# op-synth_0_8.net
KiCad netlist of a schematic drawn in EAGLE
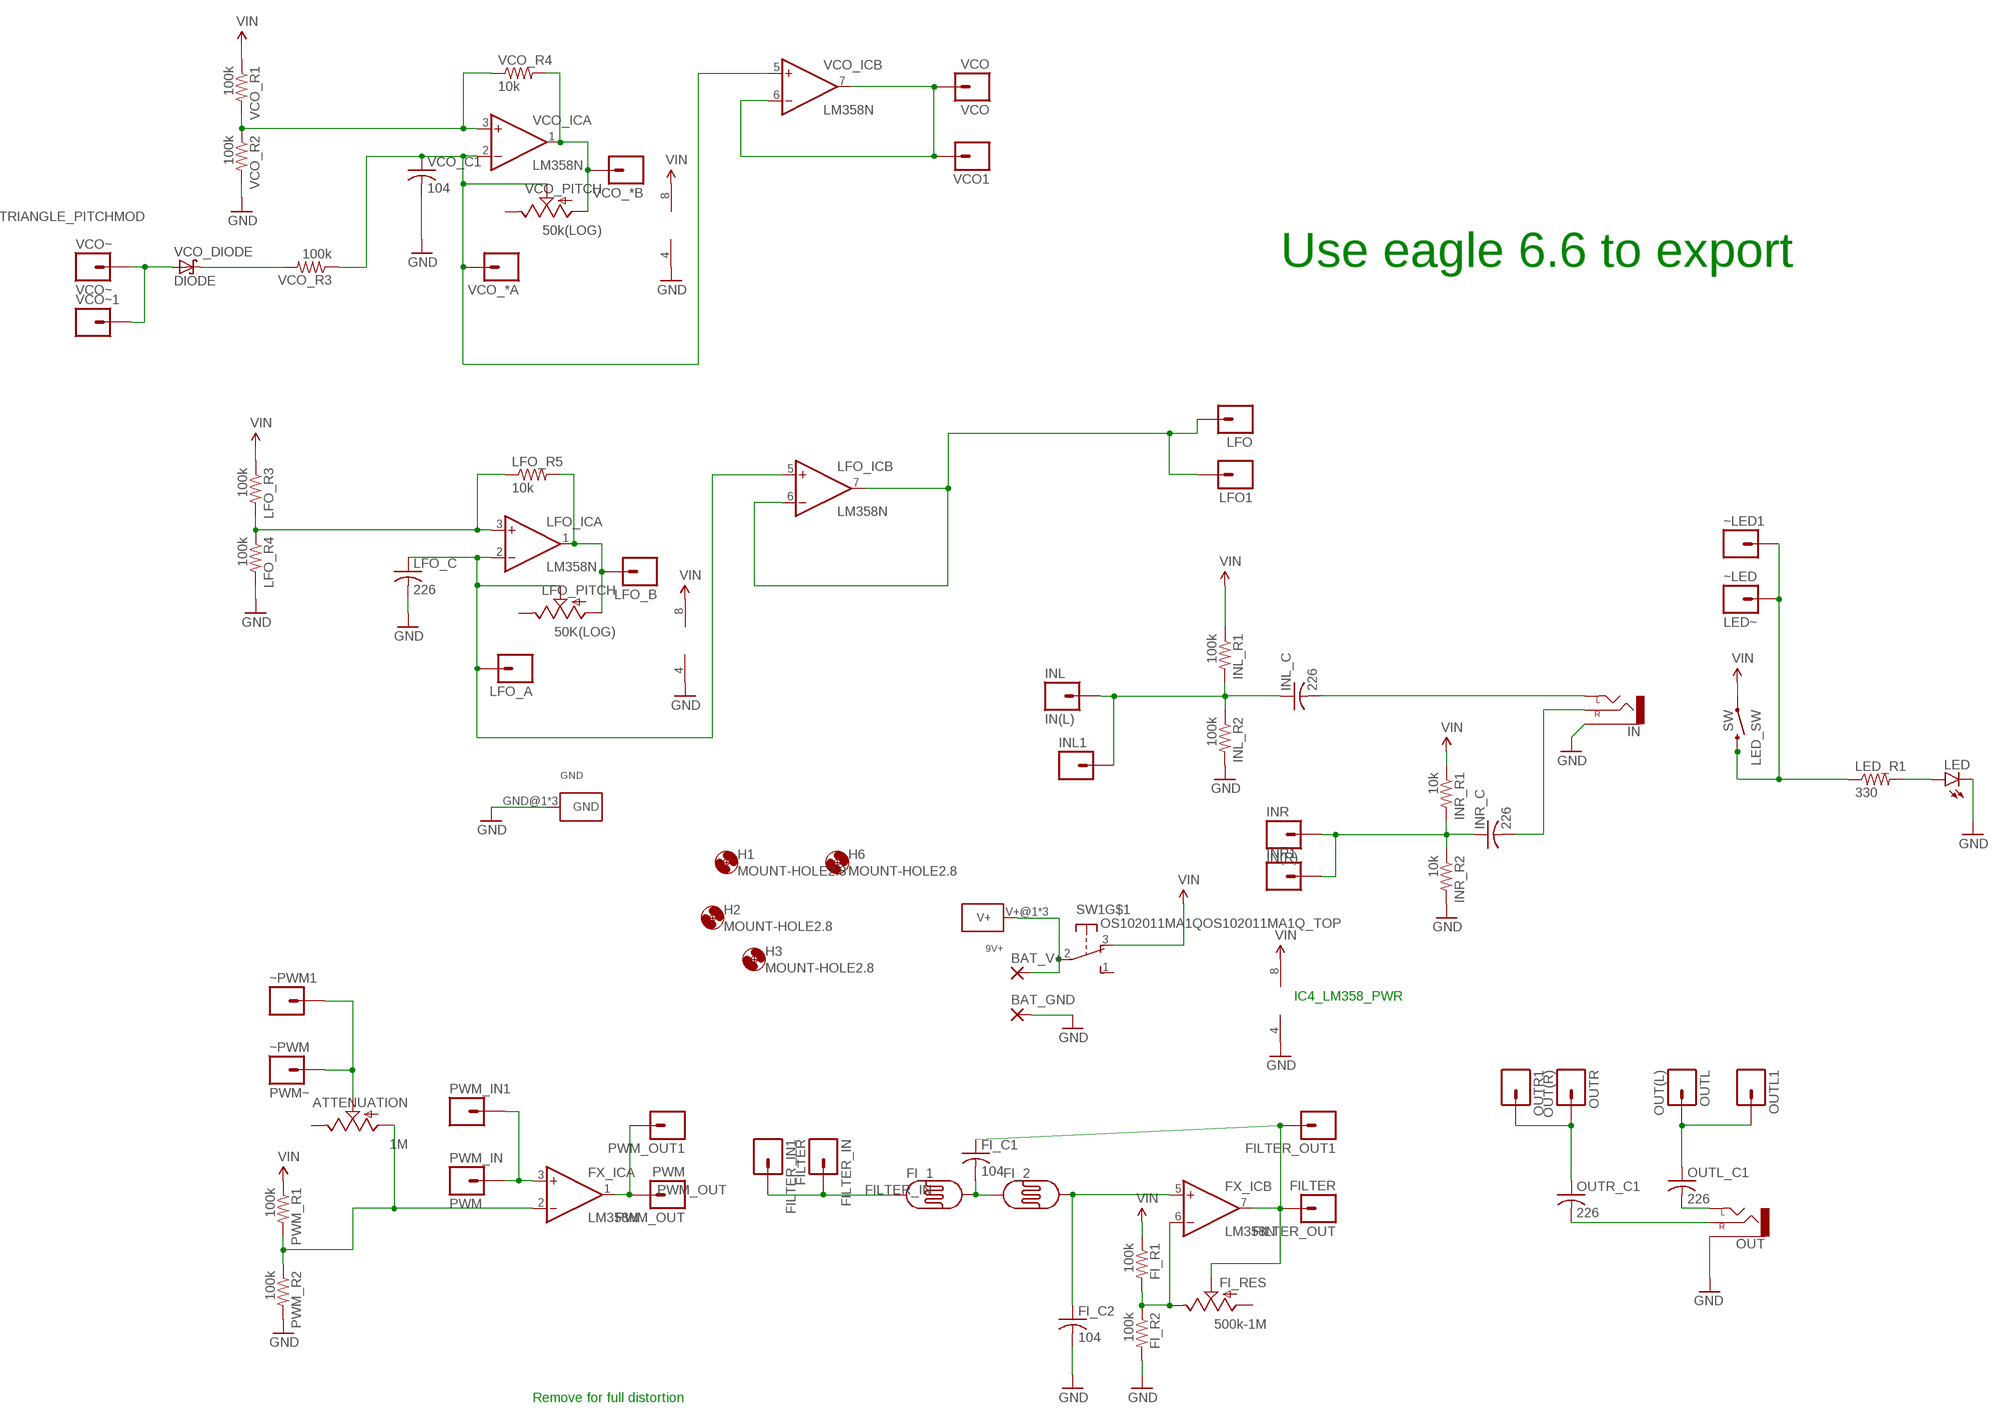
[diagram p0: schematic, sheet 1]

(export (version "E")
  (design (tool "Eeschema 10.0.6"))
  (components
    (comp (ref "9V+")
      (value "KEYSTONE-629+")
      (footprint "eagle-import:KEYSTONE_BATTAERY_TERMINAL-629+")
      (libsource (lib "eagle-import") (part "KEYSTONE-629+"))
    )
    (comp (ref "ATTENUATION")
      (value "1M")
      (footprint "eagle-import:TRIM_POT")
      (libsource (lib "eagle-import") (part "POTTRIM"))
    )
    (comp (ref "BAT_GND")
      (value "3,81/1,4")
      (footprint "eagle-import:3,81_1,4")
      (libsource (lib "eagle-import") (part "3,81/1,4"))
    )
    (comp (ref "BAT_V+")
      (value "3,81/1,4")
      (footprint "eagle-import:3,81_1,4")
      (libsource (lib "eagle-import") (part "3,81/1,4"))
    )
    (comp (ref "FILTER_IN")
      (value "FILTER")
      (footprint "eagle-import:1X01_SIDE_NAME")
      (libsource (lib "eagle-import") (part "HEADER-1X1"))
    )
    (comp (ref "FILTER_IN1")
      (value "HEADER-1X1")
      (footprint "eagle-import:1X01_SIDE_NAME")
      (libsource (lib "eagle-import") (part "HEADER-1X1"))
    )
    (comp (ref "FILTER_OUT")
      (value "FILTER")
      (footprint "eagle-import:1X01_SIDE_NAME")
      (libsource (lib "eagle-import") (part "HEADER-1X1"))
    )
    (comp (ref "FILTER_OUT1")
      (value "HEADER-1X1")
      (footprint "eagle-import:1X01_SIDE_NAME")
      (libsource (lib "eagle-import") (part "HEADER-1X1"))
    )
    (comp (ref "FI_1")
      (value "PHOTOCELLPTH")
      (footprint "eagle-import:PHOTOCELL")
      (libsource (lib "eagle-import") (part "PHOTOCELLPTH"))
    )
    (comp (ref "FI_2")
      (value "PHOTOCELLPTH")
      (footprint "eagle-import:PHOTOCELL")
      (libsource (lib "eagle-import") (part "PHOTOCELLPTH"))
    )
    (comp (ref "FI_C1")
      (value "104")
      (footprint "eagle-import:C050-024X044")
      (libsource (lib "eagle-import") (part "resistor_C-US050-024X044"))
    )
    (comp (ref "FI_C2")
      (value "104")
      (footprint "eagle-import:C050-024X044")
      (libsource (lib "eagle-import") (part "resistor_C-US050-024X044"))
    )
    (comp (ref "FI_R1")
      (value "100k")
      (footprint "eagle-import:0204_7")
      (libsource (lib "eagle-import") (part "R-US_0204/7"))
    )
    (comp (ref "FI_R2")
      (value "100k")
      (footprint "eagle-import:0204_7")
      (libsource (lib "eagle-import") (part "R-US_0204/7"))
    )
    (comp (ref "FI_RES")
      (value "500k-1M")
      (footprint "eagle-import:ALPS_POT")
      (libsource (lib "eagle-import") (part "POT"))
    )
    (comp (ref "FX_IC")
      (value "LM358N")
      (footprint "eagle-import:DIL08")
      (libsource (lib "eagle-import") (part "LM358N"))
    )
    (comp (ref "GND")
      (value "KEYSTONE-629")
      (footprint "eagle-import:KEYSTONE_AA_AAA_BATTERY_TERMINAL-629")
      (libsource (lib "eagle-import") (part "KEYSTONE-629"))
    )
    (comp (ref "H1")
      (value "MOUNT-HOLE2.8")
      (footprint "eagle-import:2,8")
      (libsource (lib "eagle-import") (part "MOUNT-HOLE2.8"))
    )
    (comp (ref "H2")
      (value "MOUNT-HOLE2.8")
      (footprint "eagle-import:2,8")
      (libsource (lib "eagle-import") (part "MOUNT-HOLE2.8"))
    )
    (comp (ref "H3")
      (value "MOUNT-HOLE2.8")
      (footprint "eagle-import:2,8")
      (libsource (lib "eagle-import") (part "MOUNT-HOLE2.8"))
    )
    (comp (ref "H6")
      (value "MOUNT-HOLE2.8")
      (footprint "eagle-import:2,8")
      (libsource (lib "eagle-import") (part "MOUNT-HOLE2.8"))
    )
    (comp (ref "IN")
      (value "AUDIO-JACKPTH")
      (footprint "eagle-import:AUDIO-JACK")
      (libsource (lib "eagle-import") (part "AUDIO-JACKPTH"))
    )
    (comp (ref "INL")
      (value "IN(L)")
      (footprint "eagle-import:1X01_SIDE_NAME")
      (libsource (lib "eagle-import") (part "HEADER-1X1"))
    )
    (comp (ref "INL1")
      (value "HEADER-1X1")
      (footprint "eagle-import:1X01_SIDE_NAME")
      (libsource (lib "eagle-import") (part "HEADER-1X1"))
    )
    (comp (ref "INL_C")
      (value "226")
      (footprint "eagle-import:C050-024X044")
      (libsource (lib "eagle-import") (part "C-US050-024X044"))
    )
    (comp (ref "INL_R1")
      (value "100k")
      (footprint "eagle-import:0204_7")
      (libsource (lib "eagle-import") (part "R-US_0204/7"))
    )
    (comp (ref "INL_R2")
      (value "100k")
      (footprint "eagle-import:0204_7")
      (libsource (lib "eagle-import") (part "R-US_0204/7"))
    )
    (comp (ref "INR")
      (value "IN(R)")
      (footprint "eagle-import:1X01_SIDE_NAME")
      (libsource (lib "eagle-import") (part "HEADER-1X1"))
    )
    (comp (ref "INR1")
      (value "HEADER-1X1")
      (footprint "eagle-import:1X01_SIDE_NAME")
      (libsource (lib "eagle-import") (part "HEADER-1X1"))
    )
    (comp (ref "INR_C")
      (value "226")
      (footprint "eagle-import:C050-024X044")
      (libsource (lib "eagle-import") (part "C-US050-024X044"))
    )
    (comp (ref "INR_R1")
      (value "10k")
      (footprint "eagle-import:0204_7")
      (libsource (lib "eagle-import") (part "R-US_0204/7"))
    )
    (comp (ref "INR_R2")
      (value "10k")
      (footprint "eagle-import:0204_7")
      (libsource (lib "eagle-import") (part "R-US_0204/7"))
    )
    (comp (ref "LED")
      (value "LED5MM")
      (footprint "eagle-import:LED5MM")
      (libsource (lib "eagle-import") (part "LED5MM"))
    )
    (comp (ref "LED_R1")
      (value "330")
      (footprint "eagle-import:0204_7")
      (libsource (lib "eagle-import") (part "R-US_0204/7"))
    )
    (comp (ref "LED_SW")
      (value "SW")
      (footprint "eagle-import:TACTILE-PTH-12MM")
      (libsource (lib "eagle-import") (part "SWITCH-MOMENTARY-212MM"))
    )
    (comp (ref "LFO")
      (value "HEADER-1X1")
      (footprint "eagle-import:1X01_SIDE_NAME")
      (libsource (lib "eagle-import") (part "HEADER-1X1"))
    )
    (comp (ref "LFO1")
      (value "HEADER-1X1")
      (footprint "eagle-import:1X01_SIDE_NAME")
      (libsource (lib "eagle-import") (part "HEADER-1X1"))
    )
    (comp (ref "LFO_A")
      (value "HEADER-1X1")
      (footprint "eagle-import:1X01_SIDE_NAME")
      (libsource (lib "eagle-import") (part "HEADER-1X1"))
    )
    (comp (ref "LFO_B")
      (value "HEADER-1X1")
      (footprint "eagle-import:1X01_SIDE_NAME")
      (libsource (lib "eagle-import") (part "HEADER-1X1"))
    )
    (comp (ref "LFO_C")
      (value "226")
      (footprint "eagle-import:C050-024X044")
      (libsource (lib "eagle-import") (part "resistor_C-US050-024X044"))
    )
    (comp (ref "LFO_IC")
      (value "LM358N")
      (footprint "eagle-import:DIL08")
      (libsource (lib "eagle-import") (part "LM358N"))
    )
    (comp (ref "LFO_PITCH")
      (value "50K(LOG)")
      (footprint "eagle-import:ALPS_POT")
      (libsource (lib "eagle-import") (part "POT"))
    )
    (comp (ref "LFO_R3")
      (value "100k")
      (footprint "eagle-import:0204_7")
      (libsource (lib "eagle-import") (part "R-US_0204/7"))
    )
    (comp (ref "LFO_R4")
      (value "100k")
      (footprint "eagle-import:0204_7")
      (libsource (lib "eagle-import") (part "R-US_0204/7"))
    )
    (comp (ref "LFO_R5")
      (value "10k")
      (footprint "eagle-import:0204_7")
      (libsource (lib "eagle-import") (part "R-US_0204/7"))
    )
    (comp (ref "OUT")
      (value "AUDIO-JACKPTH")
      (footprint "eagle-import:AUDIO-JACK")
      (libsource (lib "eagle-import") (part "AUDIO-JACKPTH"))
    )
    (comp (ref "OUTL")
      (value "OUT(L)")
      (footprint "eagle-import:1X01_SIDE_NAME")
      (libsource (lib "eagle-import") (part "HEADER-1X1"))
    )
    (comp (ref "OUTL1")
      (value "HEADER-1X1")
      (footprint "eagle-import:1X01_SIDE_NAME")
      (libsource (lib "eagle-import") (part "HEADER-1X1"))
    )
    (comp (ref "OUTL_C1")
      (value "226")
      (footprint "eagle-import:C050-024X044")
      (libsource (lib "eagle-import") (part "C-US050-024X044"))
    )
    (comp (ref "OUTR")
      (value "OUT(R)")
      (footprint "eagle-import:1X01_SIDE_NAME")
      (libsource (lib "eagle-import") (part "HEADER-1X1"))
    )
    (comp (ref "OUTR1")
      (value "HEADER-1X1")
      (footprint "eagle-import:1X01_SIDE_NAME")
      (libsource (lib "eagle-import") (part "HEADER-1X1"))
    )
    (comp (ref "OUTR_C1")
      (value "226")
      (footprint "eagle-import:C050-024X044")
      (libsource (lib "eagle-import") (part "C-US050-024X044"))
    )
    (comp (ref "PWM_IN")
      (value "PWM")
      (footprint "eagle-import:1X01_SIDE_NAME")
      (libsource (lib "eagle-import") (part "HEADER-1X1"))
    )
    (comp (ref "PWM_IN1")
      (value "HEADER-1X1")
      (footprint "eagle-import:1X01_SIDE_NAME")
      (libsource (lib "eagle-import") (part "HEADER-1X1"))
    )
    (comp (ref "PWM_OUT")
      (value "PWM")
      (footprint "eagle-import:1X01_SIDE_NAME")
      (libsource (lib "eagle-import") (part "HEADER-1X1"))
    )
    (comp (ref "PWM_OUT1")
      (value "HEADER-1X1")
      (footprint "eagle-import:1X01_SIDE_NAME")
      (libsource (lib "eagle-import") (part "HEADER-1X1"))
    )
    (comp (ref "PWM_R1")
      (value "100k")
      (footprint "eagle-import:0204_7")
      (libsource (lib "eagle-import") (part "R-US_0204/7"))
    )
    (comp (ref "PWM_R2")
      (value "100k")
      (footprint "eagle-import:0204_7")
      (libsource (lib "eagle-import") (part "R-US_0204/7"))
    )
    (comp (ref "SW1")
      (value "OS102011MA1QOS102011MA1Q_TOP")
      (footprint "eagle-import:OS102011MA1Q")
      (libsource (lib "eagle-import") (part "OS102011MA1QOS102011MA1Q_TOP"))
    )
    (comp (ref "VCO")
      (value "VCO")
      (footprint "eagle-import:1X01_SIDE_NAME")
      (libsource (lib "eagle-import") (part "HEADER-1X1"))
    )
    (comp (ref "VCO1")
      (value "HEADER-1X1")
      (footprint "eagle-import:1X01_SIDE_NAME")
      (libsource (lib "eagle-import") (part "HEADER-1X1"))
    )
    (comp (ref "VCO_*A")
      (value "HEADER-1X1")
      (footprint "eagle-import:1X01_SIDE_NAME")
      (libsource (lib "eagle-import") (part "HEADER-1X1"))
    )
    (comp (ref "VCO_*B")
      (value "HEADER-1X1")
      (footprint "eagle-import:1X01_SIDE_NAME")
      (libsource (lib "eagle-import") (part "HEADER-1X1"))
    )
    (comp (ref "VCO_C1")
      (value "104")
      (footprint "eagle-import:C050-024X044")
      (libsource (lib "eagle-import") (part "C-US050-024X044"))
    )
    (comp (ref "VCO_DIODE")
      (value "DIODE")
      (footprint "eagle-import:DO41-7")
      (libsource (lib "eagle-import") (part "SCHOTTKY-DIODEDO41-7"))
    )
    (comp (ref "VCO_IC")
      (value "LM358N")
      (footprint "eagle-import:DIL08")
      (libsource (lib "eagle-import") (part "LM358N"))
    )
    (comp (ref "VCO_PITCH")
      (value "50k(LOG)")
      (footprint "eagle-import:ALPS_POT")
      (libsource (lib "eagle-import") (part "POT"))
    )
    (comp (ref "VCO_R1")
      (value "100k")
      (footprint "eagle-import:0204_7")
      (libsource (lib "eagle-import") (part "R-US_0204/7"))
    )
    (comp (ref "VCO_R2")
      (value "100k")
      (footprint "eagle-import:0204_7")
      (libsource (lib "eagle-import") (part "R-US_0204/7"))
    )
    (comp (ref "VCO_R3")
      (value "100k")
      (footprint "eagle-import:0204_7")
      (libsource (lib "eagle-import") (part "R-US_0204/7"))
    )
    (comp (ref "VCO_R4")
      (value "10k")
      (footprint "eagle-import:0204_7")
      (libsource (lib "eagle-import") (part "R-US_0204/7"))
    )
    (comp (ref "VCO~")
      (value "VCO~")
      (footprint "eagle-import:1X01_SIDE_NAME")
      (libsource (lib "eagle-import") (part "HEADER-1X1"))
    )
    (comp (ref "VCO~1")
      (value "HEADER-1X1")
      (footprint "eagle-import:1X01_SIDE_NAME")
      (libsource (lib "eagle-import") (part "HEADER-1X1"))
    )
    (comp (ref "~LED")
      (value "LED~")
      (footprint "eagle-import:1X01_SIDE_NAME")
      (libsource (lib "eagle-import") (part "HEADER-1X1"))
    )
    (comp (ref "~LED1")
      (value "HEADER-1X1")
      (footprint "eagle-import:1X01_SIDE_NAME")
      (libsource (lib "eagle-import") (part "HEADER-1X1"))
    )
    (comp (ref "~PWM")
      (value "PWM~")
      (footprint "eagle-import:1X01_SIDE_NAME")
      (libsource (lib "eagle-import") (part "HEADER-1X1"))
    )
    (comp (ref "~PWM1")
      (value "HEADER-1X1")
      (footprint "eagle-import:1X01_SIDE_NAME")
      (libsource (lib "eagle-import") (part "HEADER-1X1"))
    )
  )
  (nets
    (net (code "1") (name "/FILTER_IN") (class "Default")
      (node (ref "FILTER_IN") (pin "1") (pinfunction "1_1") (pintype "passive"))
      (node (ref "FILTER_IN1") (pin "1") (pinfunction "1_1") (pintype "passive"))
      (node (ref "FI_1") (pin "1") (pinfunction "P$1_1") (pintype "bidirectional"))
    )
    (net (code "2") (name "/PWM_OUT") (class "Default")
      (node (ref "FX_IC") (pin "1") (pinfunction "OUT_1") (pintype "output"))
      (node (ref "PWM_OUT") (pin "1") (pinfunction "1_1") (pintype "passive"))
      (node (ref "PWM_OUT1") (pin "1") (pinfunction "1_1") (pintype "passive"))
    )
    (net (code "3") (name "/TRIANGLE_PITCHMOD") (class "Default")
      (node (ref "VCO_DIODE") (pin "A") (pinfunction "A_A") (pintype "passive"))
      (node (ref "VCO~") (pin "1") (pinfunction "1_1") (pintype "passive"))
      (node (ref "VCO~1") (pin "1") (pinfunction "1_1") (pintype "passive"))
    )
    (net (code "4") (name "GND") (class "Default")
      (node (ref "BAT_GND") (pin "1") (pinfunction "P_1") (pintype "passive"))
      (node (ref "FI_C2") (pin "2") (pinfunction "2_2") (pintype "passive"))
      (node (ref "FI_R2") (pin "2") (pinfunction "2_2") (pintype "passive"))
      (node (ref "FX_IC") (pin "4") (pinfunction "V-_4") (pintype "power_in"))
      (node (ref "GND") (pin "GND@1") (pinfunction "GND_GND@1") (pintype "power_in"))
      (node (ref "GND") (pin "GND@2") (pinfunction "GND_GND@2") (pintype "power_in"))
      (node (ref "GND") (pin "GND@3") (pinfunction "GND_GND@3") (pintype "power_in"))
      (node (ref "IN") (pin "SLEEVE") (pinfunction "SLEEVE_SLEEVE") (pintype "bidirectional"))
      (node (ref "INL_R2") (pin "2") (pinfunction "2_2") (pintype "passive"))
      (node (ref "INR_R2") (pin "2") (pinfunction "2_2") (pintype "passive"))
      (node (ref "LED") (pin "K") (pinfunction "C_K") (pintype "passive"))
      (node (ref "LFO_C") (pin "2") (pinfunction "2_2") (pintype "passive"))
      (node (ref "LFO_IC") (pin "4") (pinfunction "V-_4") (pintype "power_in"))
      (node (ref "LFO_R4") (pin "2") (pinfunction "2_2") (pintype "passive"))
      (node (ref "OUT") (pin "SLEEVE") (pinfunction "SLEEVE_SLEEVE") (pintype "bidirectional"))
      (node (ref "PWM_R2") (pin "2") (pinfunction "2_2") (pintype "passive"))
      (node (ref "VCO_C1") (pin "2") (pinfunction "2_2") (pintype "passive"))
      (node (ref "VCO_IC") (pin "4") (pinfunction "V-_4") (pintype "power_in"))
      (node (ref "VCO_R2") (pin "2") (pinfunction "2_2") (pintype "passive"))
    )
    (net (code "5") (name "Net-(ATTENUATION-A)") (class "Default")
      (node (ref "ATTENUATION") (pin "3") (pinfunction "A_3") (pintype "passive"))
      (node (ref "FX_IC") (pin "2") (pinfunction "-IN_2") (pintype "input"))
      (node (ref "PWM_R1") (pin "2") (pinfunction "2_2") (pintype "passive"))
      (node (ref "PWM_R2") (pin "1") (pinfunction "1_1") (pintype "passive"))
    )
    (net (code "6") (name "Net-(ATTENUATION-S)") (class "Default")
      (node (ref "ATTENUATION") (pin "1") (pinfunction "S_1") (pintype "passive"))
      (node (ref "~PWM") (pin "1") (pinfunction "1_1") (pintype "passive"))
      (node (ref "~PWM1") (pin "1") (pinfunction "1_1") (pintype "passive"))
    )
    (net (code "7") (name "Net-(BAT_V+-P)") (class "Default")
      (node (ref "9V+") (pin "V+@1") (pinfunction "V+_V+@1") (pintype "power_in"))
      (node (ref "9V+") (pin "V+@2") (pinfunction "V+_V+@2") (pintype "power_in"))
      (node (ref "9V+") (pin "V+@3") (pinfunction "V+_V+@3") (pintype "power_in"))
      (node (ref "BAT_V+") (pin "1") (pinfunction "P_1") (pintype "passive"))
      (node (ref "SW1") (pin "2") (pinfunction "P_2") (pintype "passive"))
    )
    (net (code "8") (name "Net-(FI_1-P$2)") (class "Default")
      (node (ref "FI_1") (pin "2") (pinfunction "P$2_2") (pintype "bidirectional"))
      (node (ref "FI_2") (pin "1") (pinfunction "P$1_1") (pintype "bidirectional"))
      (node (ref "FI_C1") (pin "2") (pinfunction "2_2") (pintype "passive"))
    )
    (net (code "9") (name "Net-(FI_2-P$2)") (class "Default")
      (node (ref "FI_2") (pin "2") (pinfunction "P$2_2") (pintype "bidirectional"))
      (node (ref "FI_C2") (pin "1") (pinfunction "1_1") (pintype "passive"))
      (node (ref "FX_IC") (pin "5") (pinfunction "+IN_5") (pintype "input"))
    )
    (net (code "10") (name "Net-(FI_RES-E)") (class "Default")
      (node (ref "FI_R1") (pin "2") (pinfunction "2_2") (pintype "passive"))
      (node (ref "FI_R2") (pin "1") (pinfunction "1_1") (pintype "passive"))
      (node (ref "FI_RES") (pin "P$1") (pinfunction "E_P$1") (pintype "passive"))
      (node (ref "FX_IC") (pin "6") (pinfunction "-IN_6") (pintype "input"))
    )
    (net (code "11") (name "Net-(FI_RES-S)") (class "Default")
      (node (ref "FILTER_OUT") (pin "1") (pinfunction "1_1") (pintype "passive"))
      (node (ref "FILTER_OUT1") (pin "1") (pinfunction "1_1") (pintype "passive"))
      (node (ref "FI_C1") (pin "1") (pinfunction "1_1") (pintype "passive"))
      (node (ref "FI_RES") (pin "P$2") (pinfunction "S_P$2") (pintype "passive"))
      (node (ref "FX_IC") (pin "7") (pinfunction "OUT_7") (pintype "output"))
    )
    (net (code "12") (name "Net-(FX_ICA-+IN)") (class "Default")
      (node (ref "FX_IC") (pin "3") (pinfunction "+IN_3") (pintype "input"))
      (node (ref "PWM_IN") (pin "1") (pinfunction "1_1") (pintype "passive"))
      (node (ref "PWM_IN1") (pin "1") (pinfunction "1_1") (pintype "passive"))
    )
    (net (code "13") (name "Net-(IN-LEFT)") (class "Default")
      (node (ref "IN") (pin "TIP") (pinfunction "LEFT_TIP") (pintype "bidirectional"))
      (node (ref "INL_C") (pin "2") (pinfunction "2_2") (pintype "passive"))
    )
    (net (code "14") (name "Net-(IN-RIGHT)") (class "Default")
      (node (ref "IN") (pin "RING") (pinfunction "RIGHT_RING") (pintype "bidirectional"))
      (node (ref "INR_C") (pin "2") (pinfunction "2_2") (pintype "passive"))
    )
    (net (code "15") (name "Net-(INL-Pad1)") (class "Default")
      (node (ref "INL") (pin "1") (pinfunction "1_1") (pintype "passive"))
      (node (ref "INL1") (pin "1") (pinfunction "1_1") (pintype "passive"))
      (node (ref "INL_C") (pin "1") (pinfunction "1_1") (pintype "passive"))
      (node (ref "INL_R1") (pin "2") (pinfunction "2_2") (pintype "passive"))
      (node (ref "INL_R2") (pin "1") (pinfunction "1_1") (pintype "passive"))
    )
    (net (code "16") (name "Net-(INR-Pad1)") (class "Default")
      (node (ref "INR") (pin "1") (pinfunction "1_1") (pintype "passive"))
      (node (ref "INR1") (pin "1") (pinfunction "1_1") (pintype "passive"))
      (node (ref "INR_C") (pin "1") (pinfunction "1_1") (pintype "passive"))
      (node (ref "INR_R1") (pin "2") (pinfunction "2_2") (pintype "passive"))
      (node (ref "INR_R2") (pin "1") (pinfunction "1_1") (pintype "passive"))
    )
    (net (code "17") (name "Net-(LED-PadA)") (class "Default")
      (node (ref "LED") (pin "A") (pinfunction "A_A") (pintype "passive"))
      (node (ref "LED_R1") (pin "2") (pinfunction "2_2") (pintype "passive"))
    )
    (net (code "18") (name "Net-(LED_SW-2)") (class "Default")
      (node (ref "LED_R1") (pin "1") (pinfunction "1_1") (pintype "passive"))
      (node (ref "LED_SW") (pin "3") (pinfunction "2_3") (pintype "passive"))
      (node (ref "~LED") (pin "1") (pinfunction "1_1") (pintype "passive"))
      (node (ref "~LED1") (pin "1") (pinfunction "1_1") (pintype "passive"))
    )
    (net (code "19") (name "Net-(LFO_ICA-+IN)") (class "Default")
      (node (ref "LFO_IC") (pin "3") (pinfunction "+IN_3") (pintype "input"))
      (node (ref "LFO_R3") (pin "2") (pinfunction "2_2") (pintype "passive"))
      (node (ref "LFO_R4") (pin "1") (pinfunction "1_1") (pintype "passive"))
      (node (ref "LFO_R5") (pin "1") (pinfunction "1_1") (pintype "passive"))
    )
    (net (code "20") (name "Net-(LFO_ICA--IN)") (class "Default")
      (node (ref "LFO_A") (pin "1") (pinfunction "1_1") (pintype "passive"))
      (node (ref "LFO_C") (pin "1") (pinfunction "1_1") (pintype "passive"))
      (node (ref "LFO_IC") (pin "2") (pinfunction "-IN_2") (pintype "input"))
      (node (ref "LFO_IC") (pin "5") (pinfunction "+IN_5") (pintype "input"))
      (node (ref "LFO_PITCH") (pin "P$2") (pinfunction "S_P$2") (pintype "passive"))
    )
    (net (code "21") (name "Net-(LFO_ICA-OUT)") (class "Default")
      (node (ref "LFO_B") (pin "1") (pinfunction "1_1") (pintype "passive"))
      (node (ref "LFO_IC") (pin "1") (pinfunction "OUT_1") (pintype "output"))
      (node (ref "LFO_PITCH") (pin "P$3") (pinfunction "A_P$3") (pintype "passive"))
      (node (ref "LFO_R5") (pin "2") (pinfunction "2_2") (pintype "passive"))
    )
    (net (code "22") (name "Net-(LFO_ICB--IN)") (class "Default")
      (node (ref "LFO") (pin "1") (pinfunction "1_1") (pintype "passive"))
      (node (ref "LFO1") (pin "1") (pinfunction "1_1") (pintype "passive"))
      (node (ref "LFO_IC") (pin "6") (pinfunction "-IN_6") (pintype "input"))
      (node (ref "LFO_IC") (pin "7") (pinfunction "OUT_7") (pintype "output"))
    )
    (net (code "23") (name "Net-(OUT-LEFT)") (class "Default")
      (node (ref "OUT") (pin "TIP") (pinfunction "LEFT_TIP") (pintype "bidirectional"))
      (node (ref "OUTL_C1") (pin "2") (pinfunction "2_2") (pintype "passive"))
    )
    (net (code "24") (name "Net-(OUT-RIGHT)") (class "Default")
      (node (ref "OUT") (pin "RING") (pinfunction "RIGHT_RING") (pintype "bidirectional"))
      (node (ref "OUTR_C1") (pin "2") (pinfunction "2_2") (pintype "passive"))
    )
    (net (code "25") (name "Net-(OUTL-Pad1)") (class "Default")
      (node (ref "OUTL") (pin "1") (pinfunction "1_1") (pintype "passive"))
      (node (ref "OUTL1") (pin "1") (pinfunction "1_1") (pintype "passive"))
      (node (ref "OUTL_C1") (pin "1") (pinfunction "1_1") (pintype "passive"))
    )
    (net (code "26") (name "Net-(OUTR-Pad1)") (class "Default")
      (node (ref "OUTR") (pin "1") (pinfunction "1_1") (pintype "passive"))
      (node (ref "OUTR1") (pin "1") (pinfunction "1_1") (pintype "passive"))
      (node (ref "OUTR_C1") (pin "1") (pinfunction "1_1") (pintype "passive"))
    )
    (net (code "27") (name "Net-(VCO_DIODE-PadC)") (class "Default")
      (node (ref "VCO_DIODE") (pin "C") (pinfunction "C_C") (pintype "passive"))
      (node (ref "VCO_R3") (pin "2") (pinfunction "2_2") (pintype "passive"))
    )
    (net (code "28") (name "Net-(VCO_ICA-+IN)") (class "Default")
      (node (ref "VCO_IC") (pin "3") (pinfunction "+IN_3") (pintype "input"))
      (node (ref "VCO_R1") (pin "2") (pinfunction "2_2") (pintype "passive"))
      (node (ref "VCO_R2") (pin "1") (pinfunction "1_1") (pintype "passive"))
      (node (ref "VCO_R4") (pin "1") (pinfunction "1_1") (pintype "passive"))
    )
    (net (code "29") (name "Net-(VCO_ICA--IN)") (class "Default")
      (node (ref "VCO_*A") (pin "1") (pinfunction "1_1") (pintype "passive"))
      (node (ref "VCO_C1") (pin "1") (pinfunction "1_1") (pintype "passive"))
      (node (ref "VCO_IC") (pin "2") (pinfunction "-IN_2") (pintype "input"))
      (node (ref "VCO_IC") (pin "5") (pinfunction "+IN_5") (pintype "input"))
      (node (ref "VCO_PITCH") (pin "P$2") (pinfunction "S_P$2") (pintype "passive"))
      (node (ref "VCO_R3") (pin "1") (pinfunction "1_1") (pintype "passive"))
    )
    (net (code "30") (name "Net-(VCO_ICA-OUT)") (class "Default")
      (node (ref "VCO_*B") (pin "1") (pinfunction "1_1") (pintype "passive"))
      (node (ref "VCO_IC") (pin "1") (pinfunction "OUT_1") (pintype "output"))
      (node (ref "VCO_PITCH") (pin "P$3") (pinfunction "A_P$3") (pintype "passive"))
      (node (ref "VCO_R4") (pin "2") (pinfunction "2_2") (pintype "passive"))
    )
    (net (code "31") (name "Net-(VCO_ICB--IN)") (class "Default")
      (node (ref "VCO") (pin "1") (pinfunction "1_1") (pintype "passive"))
      (node (ref "VCO1") (pin "1") (pinfunction "1_1") (pintype "passive"))
      (node (ref "VCO_IC") (pin "6") (pinfunction "-IN_6") (pintype "input"))
      (node (ref "VCO_IC") (pin "7") (pinfunction "OUT_7") (pintype "output"))
    )
    (net (code "32") (name "VIN") (class "Default")
      (node (ref "FI_R1") (pin "1") (pinfunction "1_1") (pintype "passive"))
      (node (ref "FX_IC") (pin "8") (pinfunction "V+_8") (pintype "power_in"))
      (node (ref "INL_R1") (pin "1") (pinfunction "1_1") (pintype "passive"))
      (node (ref "INR_R1") (pin "1") (pinfunction "1_1") (pintype "passive"))
      (node (ref "LED_SW") (pin "1") (pinfunction "1_1") (pintype "passive"))
      (node (ref "LFO_IC") (pin "8") (pinfunction "V+_8") (pintype "power_in"))
      (node (ref "LFO_R3") (pin "1") (pinfunction "1_1") (pintype "passive"))
      (node (ref "PWM_R1") (pin "1") (pinfunction "1_1") (pintype "passive"))
      (node (ref "SW1") (pin "3") (pinfunction "O_3") (pintype "passive"))
      (node (ref "VCO_IC") (pin "8") (pinfunction "V+_8") (pintype "power_in"))
      (node (ref "VCO_R1") (pin "1") (pinfunction "1_1") (pintype "passive"))
    )
    (net (code "33") (name "unconnected-(ATTENUATION-E-Pad2)") (class "Default")
      (node (ref "ATTENUATION") (pin "2") (pinfunction "E_2") (pintype "passive"))
    )
    (net (code "34") (name "unconnected-(FI_RES-A-PadP$3)") (class "Default")
      (node (ref "FI_RES") (pin "P$3") (pinfunction "A_P$3") (pintype "passive"))
    )
    (net (code "35") (name "unconnected-(LFO_PITCH-E-PadP$1)") (class "Default")
      (node (ref "LFO_PITCH") (pin "P$1") (pinfunction "E_P$1") (pintype "passive"))
    )
    (net (code "36") (name "unconnected-(SW1A-S-Pad1)") (class "Default")
      (node (ref "SW1") (pin "1") (pinfunction "S_1") (pintype "passive"))
    )
    (net (code "37") (name "unconnected-(VCO_PITCH-E-PadP$1)") (class "Default")
      (node (ref "VCO_PITCH") (pin "P$1") (pinfunction "E_P$1") (pintype "passive"))
    )
  )
)
